# Display.net
KiCad netlist of a schematic drawn in Altium Designer
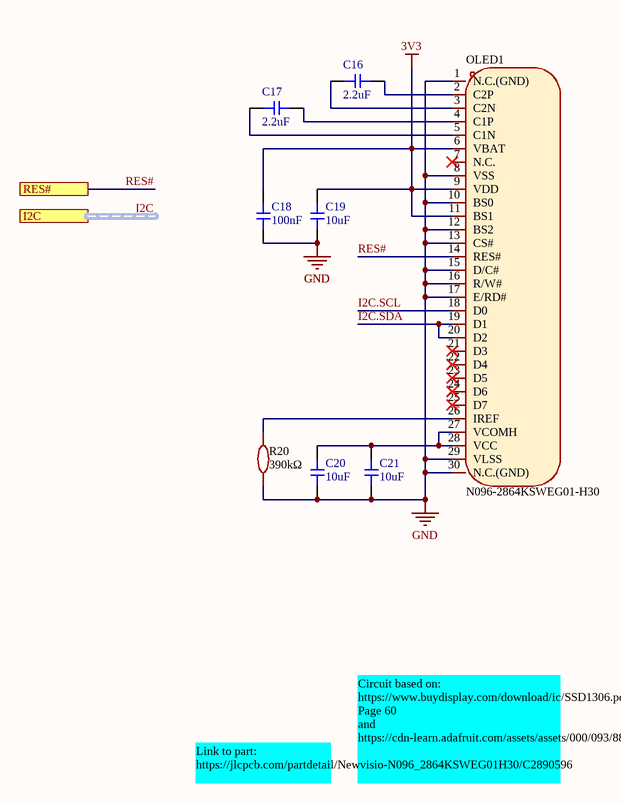
[diagram p0: Display.SchDoc]

(export (version "E")
  (design (tool "Eeschema 10.0.6"))
  (components
    (comp (ref "C16")
      (value "CL05A225MQ5NSNC")
      (footprint "CAP-0402")
      (description "Capacitor, Ceramic (MLCC), 2.2uF, ±20%, 6.3V, X5R, ±20%, SMD 0402")
      (fields
        (field (name "JLCPCB BASIC PART") "Yes")
        (field (name "CAPACITANCE") "2.2uF")
        (field (name "JLCPCB PART NUMBER") "C12530")
      )
      (libsource (lib "jlcpcb_2024_10_capacitors_basic") (part "CL05A225MQ5NSNC"))
    )
    (comp (ref "C17")
      (value "CL05A225MQ5NSNC")
      (footprint "CAP-0402")
      (description "Capacitor, Ceramic (MLCC), 2.2uF, ±20%, 6.3V, X5R, ±20%, SMD 0402")
      (fields
        (field (name "JLCPCB BASIC PART") "Yes")
        (field (name "CAPACITANCE") "2.2uF")
        (field (name "JLCPCB PART NUMBER") "C12530")
      )
      (libsource (lib "jlcpcb_2024_10_capacitors_basic") (part "CL05A225MQ5NSNC"))
    )
    (comp (ref "C18")
      (value "CL05B104KO5NNNC")
      (footprint "CAP-0402")
      (description "Capacitor, Ceramic (MLCC), 100nF, ±10%, 16V, X7R, ±10%, SMD 0402")
      (fields
        (field (name "JLCPCB BASIC PART") "Yes")
        (field (name "CAPACITANCE") "100nF")
        (field (name "JLCPCB PART NUMBER") "C1525")
      )
      (libsource (lib "jlcpcb_2024_10_capacitors_basic") (part "CL05B104KO5NNNC"))
    )
    (comp (ref "C19")
      (value "CL05A106MQ5NUNC")
      (footprint "CAP-0402")
      (description "Capacitor, Ceramic (MLCC), 10uF, ±20%, 6.3V, X5R, ±20%, SMD 0402")
      (fields
        (field (name "JLCPCB BASIC PART") "Yes")
        (field (name "CAPACITANCE") "10uF")
        (field (name "JLCPCB PART NUMBER") "C15525")
      )
      (libsource (lib "jlcpcb_2024_10_capacitors_basic") (part "CL05A106MQ5NUNC"))
    )
    (comp (ref "C20")
      (value "CL05A106MQ5NUNC")
      (footprint "CAP-0402")
      (description "Capacitor, Ceramic (MLCC), 10uF, ±20%, 6.3V, X5R, ±20%, SMD 0402")
      (fields
        (field (name "JLCPCB BASIC PART") "Yes")
        (field (name "CAPACITANCE") "10uF")
        (field (name "JLCPCB PART NUMBER") "C15525")
      )
      (libsource (lib "jlcpcb_2024_10_capacitors_basic") (part "CL05A106MQ5NUNC"))
    )
    (comp (ref "C21")
      (value "CL05A106MQ5NUNC")
      (footprint "CAP-0402")
      (description "Capacitor, Ceramic (MLCC), 10uF, ±20%, 6.3V, X5R, ±20%, SMD 0402")
      (fields
        (field (name "JLCPCB BASIC PART") "Yes")
        (field (name "CAPACITANCE") "10uF")
        (field (name "JLCPCB PART NUMBER") "C15525")
      )
      (libsource (lib "jlcpcb_2024_10_capacitors_basic") (part "CL05A106MQ5NUNC"))
    )
    (comp (ref "OLED1")
      (value "N096-2864KSWEG01-H30")
      (footprint "OLED_0.96-30P-P0.70-12864")
      (fields (field (name "MANUFACTURER") "Newvision(新智景)"))
      (libsource (lib "N096-2864KSWEG01-H301_N096-2864KSWEG01-H30") (part "N096-2864KSWEG01-H30"))
    )
    (comp (ref "R20")
      (value "390kΩ")
      (footprint "R0402")
      (description "390k Resistor")
      (fields
        (field (name "MANUFACTURER") "UNI-ROYAL(厚声)")
        (field (name "MANUFACTURER PART") "0402WGF3903TCE")
      )
      (libsource (lib "0402WGF3903TCE1_0402WGF3903TCE") (part "0402WGF3903TCE"))
    )
  )
  (nets
    (net (code "2") (name "/I2C.SCL") (class "Default")
      (node (ref "OLED1") (pin "18") (pinfunction "D0_18") (pintype "passive"))
    )
    (net (code "3") (name "/I2C.SDA") (class "Default")
      (node (ref "OLED1") (pin "19") (pinfunction "D1_19") (pintype "passive"))
      (node (ref "OLED1") (pin "20") (pinfunction "D2_20") (pintype "passive"))
    )
    (net (code "4") (name "/RES#") (class "Default")
      (node (ref "OLED1") (pin "14") (pinfunction "RES#_14") (pintype "passive"))
    )
    (net (code "6") (name "3V3") (class "Default")
      (node (ref "C18") (pin "2") (pinfunction "2_2") (pintype "passive"))
      (node (ref "C19") (pin "2") (pinfunction "2_2") (pintype "passive"))
      (node (ref "OLED1") (pin "11") (pinfunction "BS1_11") (pintype "passive"))
      (node (ref "OLED1") (pin "6") (pinfunction "VBAT_6") (pintype "passive"))
      (node (ref "OLED1") (pin "9") (pinfunction "VDD_9") (pintype "passive"))
    )
    (net (code "7") (name "GND") (class "Default")
      (node (ref "C18") (pin "1") (pinfunction "1_1") (pintype "passive"))
      (node (ref "C19") (pin "1") (pinfunction "1_1") (pintype "passive"))
      (node (ref "C20") (pin "1") (pinfunction "1_1") (pintype "passive"))
      (node (ref "C21") (pin "1") (pinfunction "1_1") (pintype "passive"))
      (node (ref "OLED1") (pin "1") (pinfunction "N.C.(GND)_1") (pintype "passive"))
      (node (ref "OLED1") (pin "10") (pinfunction "BS0_10") (pintype "passive"))
      (node (ref "OLED1") (pin "12") (pinfunction "BS2_12") (pintype "passive"))
      (node (ref "OLED1") (pin "13") (pinfunction "CS#_13") (pintype "passive"))
      (node (ref "OLED1") (pin "15") (pinfunction "D/C#_15") (pintype "passive"))
      (node (ref "OLED1") (pin "16") (pinfunction "R/W#_16") (pintype "passive"))
      (node (ref "OLED1") (pin "17") (pinfunction "E/RD#_17") (pintype "passive"))
      (node (ref "OLED1") (pin "29") (pinfunction "VLSS_29") (pintype "passive"))
      (node (ref "OLED1") (pin "30") (pinfunction "N.C.(GND)_30") (pintype "passive"))
      (node (ref "OLED1") (pin "8") (pinfunction "VSS_8") (pintype "passive"))
      (node (ref "R20") (pin "1") (pinfunction "1_1") (pintype "passive"))
    )
    (net (code "8") (name "Net-(OLED1-C1N)") (class "Default")
      (node (ref "C17") (pin "1") (pinfunction "1_1") (pintype "passive"))
      (node (ref "OLED1") (pin "5") (pinfunction "C1N_5") (pintype "passive"))
    )
    (net (code "9") (name "Net-(OLED1-C1P)") (class "Default")
      (node (ref "C17") (pin "2") (pinfunction "2_2") (pintype "passive"))
      (node (ref "OLED1") (pin "4") (pinfunction "C1P_4") (pintype "passive"))
    )
    (net (code "10") (name "Net-(OLED1-C2N)") (class "Default")
      (node (ref "C16") (pin "1") (pinfunction "1_1") (pintype "passive"))
      (node (ref "OLED1") (pin "3") (pinfunction "C2N_3") (pintype "passive"))
    )
    (net (code "11") (name "Net-(OLED1-C2P)") (class "Default")
      (node (ref "C16") (pin "2") (pinfunction "2_2") (pintype "passive"))
      (node (ref "OLED1") (pin "2") (pinfunction "C2P_2") (pintype "passive"))
    )
    (net (code "12") (name "Net-(OLED1-IREF)") (class "Default")
      (node (ref "OLED1") (pin "26") (pinfunction "IREF_26") (pintype "passive"))
      (node (ref "R20") (pin "2") (pinfunction "2_2") (pintype "passive"))
    )
    (net (code "13") (name "Net-(OLED1-VCC)") (class "Default")
      (node (ref "C20") (pin "2") (pinfunction "2_2") (pintype "passive"))
      (node (ref "C21") (pin "2") (pinfunction "2_2") (pintype "passive"))
      (node (ref "OLED1") (pin "27") (pinfunction "VCOMH_27") (pintype "passive"))
      (node (ref "OLED1") (pin "28") (pinfunction "VCC_28") (pintype "passive"))
    )
    (net (code "14") (name "unconnected-(OLED1-D3-Pad21)") (class "Default")
      (node (ref "OLED1") (pin "21") (pinfunction "D3_21") (pintype "passive+no_connect"))
    )
    (net (code "15") (name "unconnected-(OLED1-D4-Pad22)") (class "Default")
      (node (ref "OLED1") (pin "22") (pinfunction "D4_22") (pintype "passive+no_connect"))
    )
    (net (code "16") (name "unconnected-(OLED1-D5-Pad23)") (class "Default")
      (node (ref "OLED1") (pin "23") (pinfunction "D5_23") (pintype "passive+no_connect"))
    )
    (net (code "17") (name "unconnected-(OLED1-D6-Pad24)") (class "Default")
      (node (ref "OLED1") (pin "24") (pinfunction "D6_24") (pintype "passive+no_connect"))
    )
    (net (code "18") (name "unconnected-(OLED1-D7-Pad25)") (class "Default")
      (node (ref "OLED1") (pin "25") (pinfunction "D7_25") (pintype "passive+no_connect"))
    )
    (net (code "19") (name "unconnected-(OLED1-N.C.-Pad7)") (class "Default")
      (node (ref "OLED1") (pin "7") (pinfunction "N.C._7") (pintype "passive+no_connect"))
    )
  )
)
